# SCH-9-Battery_Voltage_Indicators.net
KiCad netlist of a schematic drawn in Altium Designer
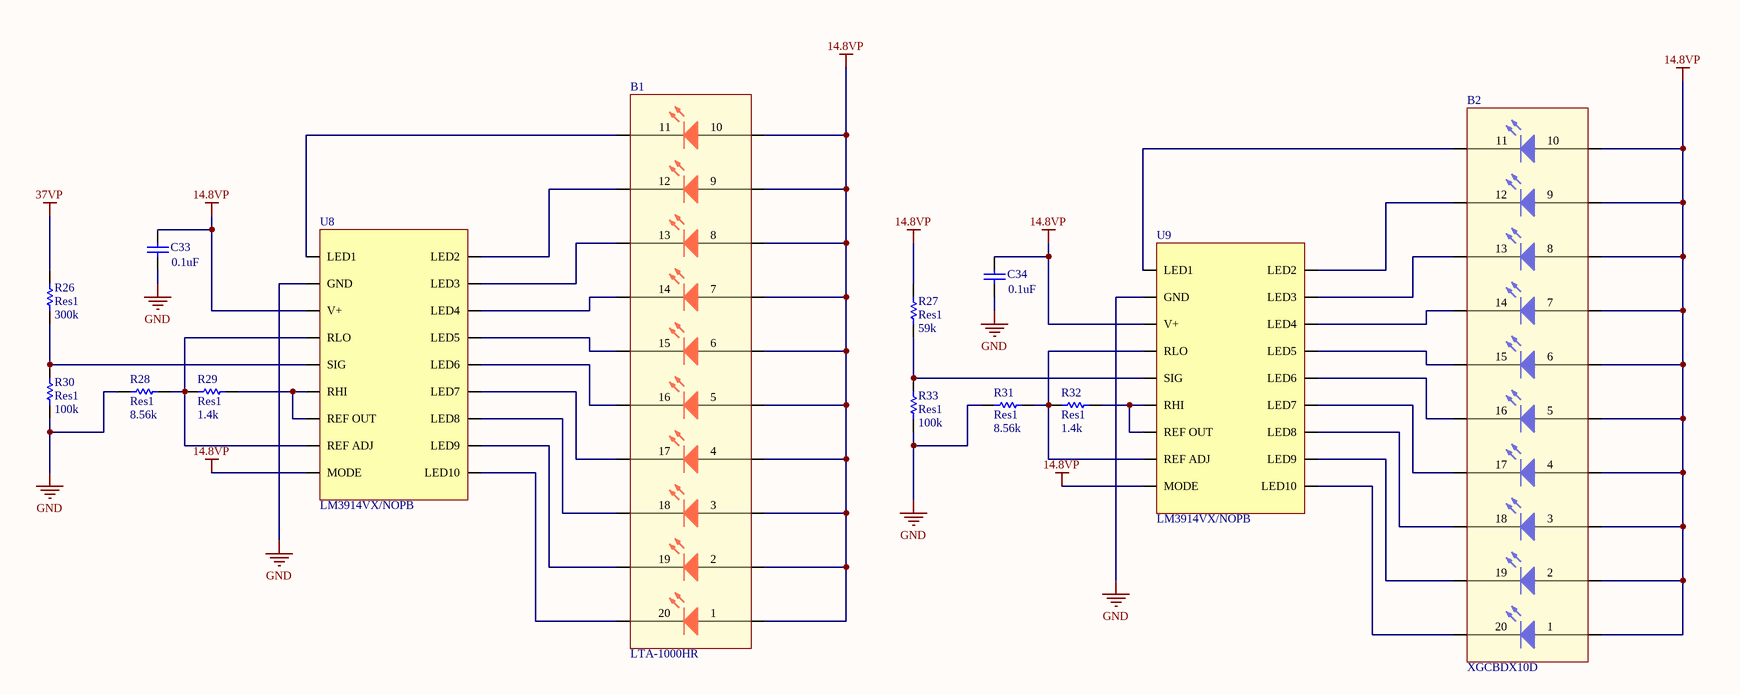
[diagram p0: SCH-9-Battery Voltage Indicators.SchDoc]

(export (version "E")
  (design (tool "Eeschema 10.0.6"))
  (components
    (comp (ref "B1")
      (value "LTA-1000HR")
      (footprint "LED BAR 10pos")
      (libsource (lib "RSX_Miscellaneous") (part "LED BAR 10 RED"))
    )
    (comp (ref "B2")
      (value "XGCBDX10D")
      (footprint "LED BAR 10pos")
      (libsource (lib "RSX_Miscellaneous") (part "LED BAR 10 BLUE"))
    )
    (comp (ref "C33")
      (value "0.1uF")
      (footprint "C1206")
      (description "Capacitor (Semiconductor SIM Model)")
      (fields (field (name "Comment") "Cap Semi") (field (name "PUBLISHER") "Altium Limited"))
      (libsource (lib "Miscellaneous Devices") (part "Cap Semi"))
    )
    (comp (ref "C34")
      (value "0.1uF")
      (footprint "C1206")
      (description "Capacitor (Semiconductor SIM Model)")
      (fields (field (name "Comment") "Cap Semi") (field (name "PUBLISHER") "Altium Limited"))
      (libsource (lib "Miscellaneous Devices") (part "Cap Semi"))
    )
    (comp (ref "R26")
      (value "Res1")
      (footprint "RESC1608X06N_0603")
      (description "Resistor")
      (fields (field (name "ALTIUM_VALUE") "300k") (field (name "PUBLISHER") "Altium Limited"))
      (libsource (lib "RSX_Resistors") (part "Res1"))
    )
    (comp (ref "R27")
      (value "Res1")
      (footprint "RESC1608X06N_0603")
      (description "Resistor")
      (fields (field (name "ALTIUM_VALUE") "59k") (field (name "PUBLISHER") "Altium Limited"))
      (libsource (lib "RSX_Resistors") (part "Res1"))
    )
    (comp (ref "R28")
      (value "Res1")
      (footprint "RESC1608X06N_0603")
      (description "Resistor")
      (fields (field (name "ALTIUM_VALUE") "8.56k") (field (name "PUBLISHER") "Altium Limited"))
      (libsource (lib "RSX_Resistors") (part "Res1"))
    )
    (comp (ref "R29")
      (value "Res1")
      (footprint "RESC1608X06N_0603")
      (description "Resistor")
      (fields (field (name "ALTIUM_VALUE") "1.4k") (field (name "PUBLISHER") "Altium Limited"))
      (libsource (lib "RSX_Resistors") (part "Res1"))
    )
    (comp (ref "R30")
      (value "Res1")
      (footprint "RESC1608X06N_0603")
      (description "Resistor")
      (fields (field (name "ALTIUM_VALUE") "100k") (field (name "PUBLISHER") "Altium Limited"))
      (libsource (lib "RSX_Resistors") (part "Res1"))
    )
    (comp (ref "R31")
      (value "Res1")
      (footprint "RESC1608X06N_0603")
      (description "Resistor")
      (fields (field (name "ALTIUM_VALUE") "8.56k") (field (name "PUBLISHER") "Altium Limited"))
      (libsource (lib "RSX_Resistors") (part "Res1"))
    )
    (comp (ref "R32")
      (value "Res1")
      (footprint "RESC1608X06N_0603")
      (description "Resistor")
      (fields (field (name "ALTIUM_VALUE") "1.4k") (field (name "PUBLISHER") "Altium Limited"))
      (libsource (lib "RSX_Resistors") (part "Res1"))
    )
    (comp (ref "R33")
      (value "Res1")
      (footprint "RESC1608X06N_0603")
      (description "Resistor")
      (fields (field (name "ALTIUM_VALUE") "100k") (field (name "PUBLISHER") "Altium Limited"))
      (libsource (lib "RSX_Resistors") (part "Res1"))
    )
    (comp (ref "U8")
      (value "LM3914VX/NOPB")
      (footprint "PLCC127P990X990X457-20N")
      (libsource (lib "RSX_ICs") (part "LM3914"))
    )
    (comp (ref "U9")
      (value "LM3914VX/NOPB")
      (footprint "PLCC127P990X990X457-20N")
      (libsource (lib "RSX_ICs") (part "LM3914"))
    )
  )
  (nets
    (net (code "1") (name "14.8VP") (class "Default")
      (node (ref "B1") (pin "1") (pinfunction "A_1") (pintype "passive"))
      (node (ref "B1") (pin "10") (pinfunction "A_10") (pintype "passive"))
      (node (ref "B1") (pin "2") (pinfunction "A_2") (pintype "passive"))
      (node (ref "B1") (pin "3") (pinfunction "A_3") (pintype "passive"))
      (node (ref "B1") (pin "4") (pinfunction "A_4") (pintype "passive"))
      (node (ref "B1") (pin "5") (pinfunction "A_5") (pintype "passive"))
      (node (ref "B1") (pin "6") (pinfunction "A_6") (pintype "passive"))
      (node (ref "B1") (pin "7") (pinfunction "A_7") (pintype "passive"))
      (node (ref "B1") (pin "8") (pinfunction "A_8") (pintype "passive"))
      (node (ref "B1") (pin "9") (pinfunction "A_9") (pintype "passive"))
      (node (ref "B2") (pin "1") (pinfunction "A_1") (pintype "passive"))
      (node (ref "B2") (pin "10") (pinfunction "A_10") (pintype "passive"))
      (node (ref "B2") (pin "2") (pinfunction "A_2") (pintype "passive"))
      (node (ref "B2") (pin "3") (pinfunction "A_3") (pintype "passive"))
      (node (ref "B2") (pin "4") (pinfunction "A_4") (pintype "passive"))
      (node (ref "B2") (pin "5") (pinfunction "A_5") (pintype "passive"))
      (node (ref "B2") (pin "6") (pinfunction "A_6") (pintype "passive"))
      (node (ref "B2") (pin "7") (pinfunction "A_7") (pintype "passive"))
      (node (ref "B2") (pin "8") (pinfunction "A_8") (pintype "passive"))
      (node (ref "B2") (pin "9") (pinfunction "A_9") (pintype "passive"))
      (node (ref "C33") (pin "2") (pinfunction "2_2") (pintype "passive"))
      (node (ref "C34") (pin "2") (pinfunction "2_2") (pintype "passive"))
      (node (ref "R27") (pin "2") (pinfunction "2_2") (pintype "passive"))
      (node (ref "U8") (pin "11") (pinfunction "MODE_11") (pintype "passive"))
      (node (ref "U8") (pin "3") (pinfunction "V+_3") (pintype "passive"))
      (node (ref "U9") (pin "11") (pinfunction "MODE_11") (pintype "passive"))
      (node (ref "U9") (pin "3") (pinfunction "V+_3") (pintype "passive"))
    )
    (net (code "2") (name "37VP") (class "Default")
      (node (ref "R26") (pin "2") (pinfunction "2_2") (pintype "passive"))
    )
    (net (code "3") (name "GND") (class "Default")
      (node (ref "C33") (pin "1") (pinfunction "1_1") (pintype "passive"))
      (node (ref "C34") (pin "1") (pinfunction "1_1") (pintype "passive"))
      (node (ref "R28") (pin "1") (pinfunction "1_1") (pintype "passive"))
      (node (ref "R30") (pin "1") (pinfunction "1_1") (pintype "passive"))
      (node (ref "R31") (pin "1") (pinfunction "1_1") (pintype "passive"))
      (node (ref "R33") (pin "1") (pinfunction "1_1") (pintype "passive"))
      (node (ref "U8") (pin "2") (pinfunction "GND_2") (pintype "passive"))
      (node (ref "U9") (pin "2") (pinfunction "GND_2") (pintype "passive"))
    )
    (net (code "4") (name "Net-(U8-LED1)") (class "Default")
      (node (ref "B1") (pin "11") (pinfunction "K_11") (pintype "passive"))
      (node (ref "U8") (pin "1") (pinfunction "LED1_1") (pintype "passive"))
    )
    (net (code "5") (name "Net-(U8-LED2)") (class "Default")
      (node (ref "B1") (pin "12") (pinfunction "K_12") (pintype "passive"))
      (node (ref "U8") (pin "20") (pinfunction "LED2_20") (pintype "passive"))
    )
    (net (code "6") (name "Net-(U8-LED3)") (class "Default")
      (node (ref "B1") (pin "13") (pinfunction "K_13") (pintype "passive"))
      (node (ref "U8") (pin "19") (pinfunction "LED3_19") (pintype "passive"))
    )
    (net (code "7") (name "Net-(U8-LED4)") (class "Default")
      (node (ref "B1") (pin "14") (pinfunction "K_14") (pintype "passive"))
      (node (ref "U8") (pin "18") (pinfunction "LED4_18") (pintype "passive"))
    )
    (net (code "8") (name "Net-(U8-LED5)") (class "Default")
      (node (ref "B1") (pin "15") (pinfunction "K_15") (pintype "passive"))
      (node (ref "U8") (pin "17") (pinfunction "LED5_17") (pintype "passive"))
    )
    (net (code "9") (name "Net-(U8-LED6)") (class "Default")
      (node (ref "B1") (pin "16") (pinfunction "K_16") (pintype "passive"))
      (node (ref "U8") (pin "16") (pinfunction "LED6_16") (pintype "passive"))
    )
    (net (code "10") (name "Net-(U8-LED7)") (class "Default")
      (node (ref "B1") (pin "17") (pinfunction "K_17") (pintype "passive"))
      (node (ref "U8") (pin "15") (pinfunction "LED7_15") (pintype "passive"))
    )
    (net (code "11") (name "Net-(U8-LED8)") (class "Default")
      (node (ref "B1") (pin "18") (pinfunction "K_18") (pintype "passive"))
      (node (ref "U8") (pin "14") (pinfunction "LED8_14") (pintype "passive"))
    )
    (net (code "12") (name "Net-(U8-LED9)") (class "Default")
      (node (ref "B1") (pin "19") (pinfunction "K_19") (pintype "passive"))
      (node (ref "U8") (pin "13") (pinfunction "LED9_13") (pintype "passive"))
    )
    (net (code "13") (name "Net-(U8-LED10)") (class "Default")
      (node (ref "B1") (pin "20") (pinfunction "K_20") (pintype "passive"))
      (node (ref "U8") (pin "12") (pinfunction "LED10_12") (pintype "passive"))
    )
    (net (code "14") (name "Net-(U8-REF_ADJ)") (class "Default")
      (node (ref "R28") (pin "2") (pinfunction "2_2") (pintype "passive"))
      (node (ref "R29") (pin "1") (pinfunction "1_1") (pintype "passive"))
      (node (ref "U8") (pin "10") (pinfunction "REF_ADJ_10") (pintype "passive"))
      (node (ref "U8") (pin "4") (pinfunction "RLO_4") (pintype "passive"))
    )
    (net (code "15") (name "Net-(U8-REF_OUT)") (class "Default")
      (node (ref "R29") (pin "2") (pinfunction "2_2") (pintype "passive"))
      (node (ref "U8") (pin "6") (pinfunction "RHI_6") (pintype "passive"))
      (node (ref "U8") (pin "8") (pinfunction "REF_OUT_8") (pintype "passive"))
    )
    (net (code "16") (name "Net-(U8-SIG)") (class "Default")
      (node (ref "R26") (pin "1") (pinfunction "1_1") (pintype "passive"))
      (node (ref "R30") (pin "2") (pinfunction "2_2") (pintype "passive"))
      (node (ref "U8") (pin "5") (pinfunction "SIG_5") (pintype "passive"))
    )
    (net (code "17") (name "Net-(U9-LED1)") (class "Default")
      (node (ref "B2") (pin "11") (pinfunction "K_11") (pintype "passive"))
      (node (ref "U9") (pin "1") (pinfunction "LED1_1") (pintype "passive"))
    )
    (net (code "18") (name "Net-(U9-LED2)") (class "Default")
      (node (ref "B2") (pin "12") (pinfunction "K_12") (pintype "passive"))
      (node (ref "U9") (pin "20") (pinfunction "LED2_20") (pintype "passive"))
    )
    (net (code "19") (name "Net-(U9-LED3)") (class "Default")
      (node (ref "B2") (pin "13") (pinfunction "K_13") (pintype "passive"))
      (node (ref "U9") (pin "19") (pinfunction "LED3_19") (pintype "passive"))
    )
    (net (code "20") (name "Net-(U9-LED4)") (class "Default")
      (node (ref "B2") (pin "14") (pinfunction "K_14") (pintype "passive"))
      (node (ref "U9") (pin "18") (pinfunction "LED4_18") (pintype "passive"))
    )
    (net (code "21") (name "Net-(U9-LED5)") (class "Default")
      (node (ref "B2") (pin "15") (pinfunction "K_15") (pintype "passive"))
      (node (ref "U9") (pin "17") (pinfunction "LED5_17") (pintype "passive"))
    )
    (net (code "22") (name "Net-(U9-LED6)") (class "Default")
      (node (ref "B2") (pin "16") (pinfunction "K_16") (pintype "passive"))
      (node (ref "U9") (pin "16") (pinfunction "LED6_16") (pintype "passive"))
    )
    (net (code "23") (name "Net-(U9-LED7)") (class "Default")
      (node (ref "B2") (pin "17") (pinfunction "K_17") (pintype "passive"))
      (node (ref "U9") (pin "15") (pinfunction "LED7_15") (pintype "passive"))
    )
    (net (code "24") (name "Net-(U9-LED8)") (class "Default")
      (node (ref "B2") (pin "18") (pinfunction "K_18") (pintype "passive"))
      (node (ref "U9") (pin "14") (pinfunction "LED8_14") (pintype "passive"))
    )
    (net (code "25") (name "Net-(U9-LED9)") (class "Default")
      (node (ref "B2") (pin "19") (pinfunction "K_19") (pintype "passive"))
      (node (ref "U9") (pin "13") (pinfunction "LED9_13") (pintype "passive"))
    )
    (net (code "26") (name "Net-(U9-LED10)") (class "Default")
      (node (ref "B2") (pin "20") (pinfunction "K_20") (pintype "passive"))
      (node (ref "U9") (pin "12") (pinfunction "LED10_12") (pintype "passive"))
    )
    (net (code "27") (name "Net-(U9-REF_ADJ)") (class "Default")
      (node (ref "R31") (pin "2") (pinfunction "2_2") (pintype "passive"))
      (node (ref "R32") (pin "1") (pinfunction "1_1") (pintype "passive"))
      (node (ref "U9") (pin "10") (pinfunction "REF_ADJ_10") (pintype "passive"))
      (node (ref "U9") (pin "4") (pinfunction "RLO_4") (pintype "passive"))
    )
    (net (code "28") (name "Net-(U9-REF_OUT)") (class "Default")
      (node (ref "R32") (pin "2") (pinfunction "2_2") (pintype "passive"))
      (node (ref "U9") (pin "6") (pinfunction "RHI_6") (pintype "passive"))
      (node (ref "U9") (pin "8") (pinfunction "REF_OUT_8") (pintype "passive"))
    )
    (net (code "29") (name "Net-(U9-SIG)") (class "Default")
      (node (ref "R27") (pin "1") (pinfunction "1_1") (pintype "passive"))
      (node (ref "R33") (pin "2") (pinfunction "2_2") (pintype "passive"))
      (node (ref "U9") (pin "5") (pinfunction "SIG_5") (pintype "passive"))
    )
  )
)
